# Sheet1.net
KiCad netlist of a schematic drawn in Altium Designer
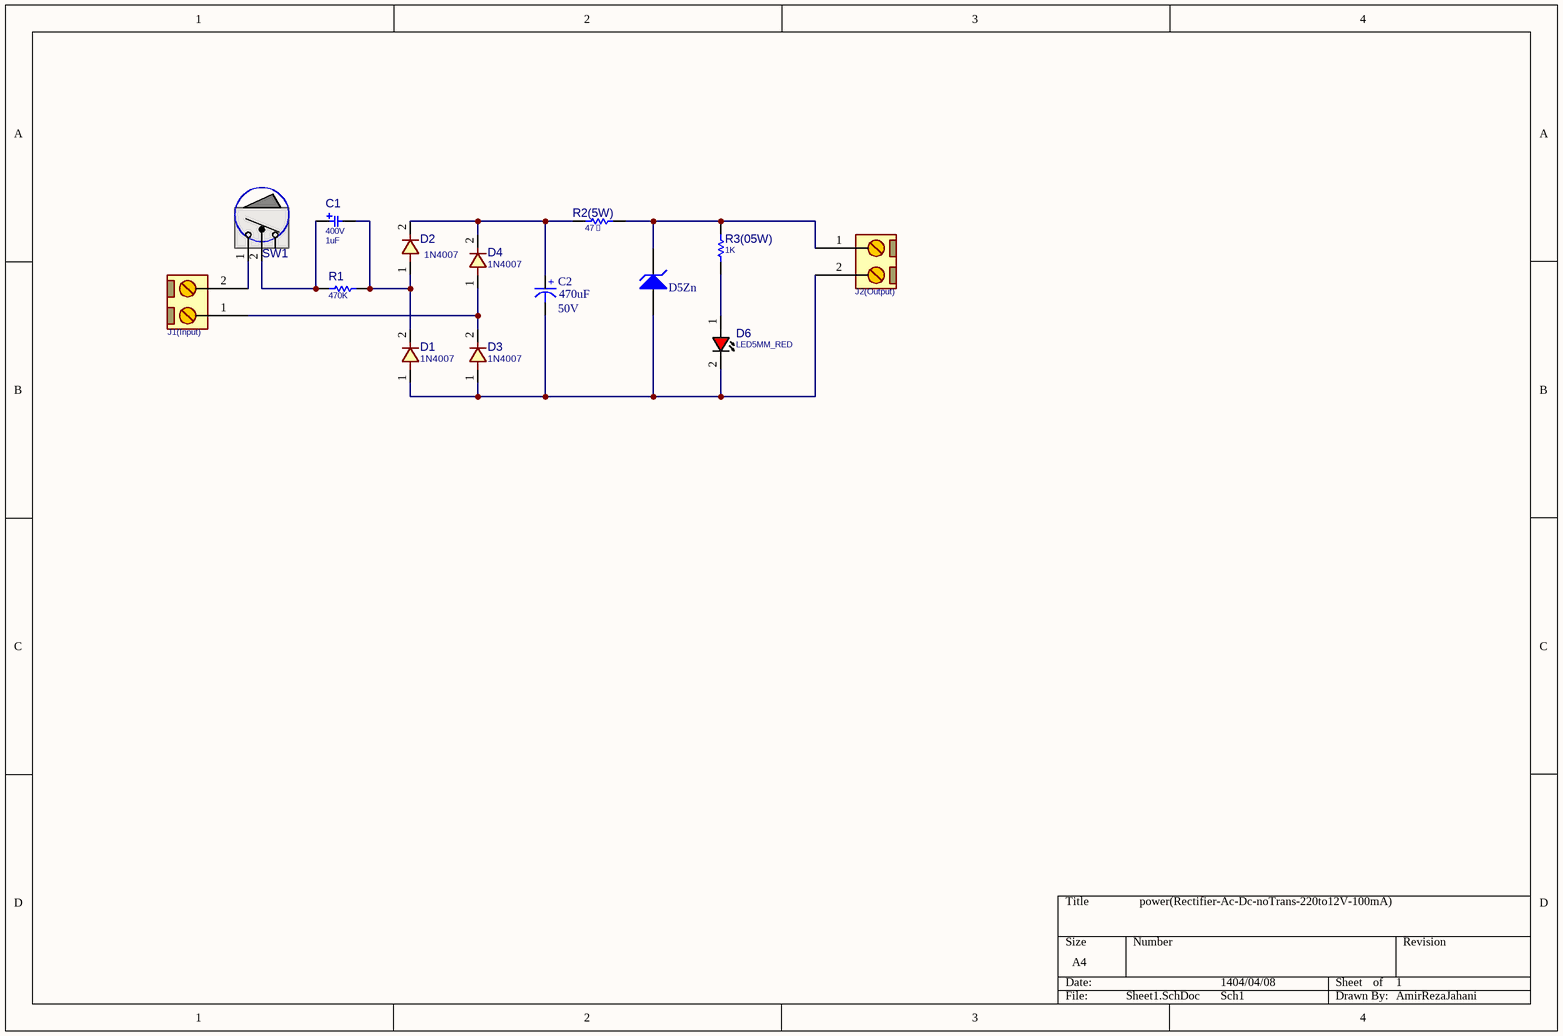
[diagram p0: Sheet1.SchDoc]

(export (version "E")
  (design (tool "Eeschema 10.0.6"))
  (components
    (comp (ref "C1")
      (value "1uF")
      (footprint "C_FLM_22X7H14")
      (description "CAP, THD, FILM,")
      (fields
        (field (name "MANF_P#") "MANF_PART#")
        (field (name "MANF") "MANF")
        (field (name "PARAM2") "400V")
      )
      (libsource (lib "passive_thd") (part "CAP_THD_FLM_0.47uF_400v"))
    )
    (comp (ref "C2")
      (value "470uF")
      (footprint "cap 03")
      (description "Polar Capacitor")
      (fields (field (name "VOLTAGE") "50V") (field (name "DESIGNER") "Saeid Jorablo"))
      (libsource (lib "My_Library") (part "Cap-Polar"))
    )
    (comp (ref "D1")
      (value "1N4007")
      (footprint "D_AX04_DO41")
      (description "DIODE, THD")
      (fields (field (name "MANF") "MANF") (field (name "MANF_P#") "1N4001"))
      (libsource (lib "diode") (part "DIODE_THD"))
    )
    (comp (ref "D2")
      (value "1N4007")
      (footprint "D_AX04_DO41")
      (description "DIODE, THD")
      (fields (field (name "MANF") "MANF") (field (name "MANF_P#") "1N4001"))
      (libsource (lib "diode") (part "DIODE_THD"))
    )
    (comp (ref "D3")
      (value "1N4007")
      (footprint "D_AX04_DO41")
      (description "DIODE, THD")
      (fields (field (name "MANF") "MANF") (field (name "MANF_P#") "1N4001"))
      (libsource (lib "diode") (part "DIODE_THD"))
    )
    (comp (ref "D4")
      (value "1N4007")
      (footprint "D_AX04_DO41")
      (description "DIODE, THD")
      (fields (field (name "MANF") "MANF") (field (name "MANF_P#") "1N4001"))
      (libsource (lib "diode") (part "DIODE_THD"))
    )
    (comp (ref "D5Zn")
      (value "Diode Zener")
      (footprint "Diode 1W")
      (description "Zener Diode")
      (fields (field (name "VOLTAGE") "3.3 V") (field (name "DESIGNER") "Saeid Jorablo"))
      (libsource (lib "My_Library") (part "Diode Zener"))
    )
    (comp (ref "D6")
      (value "LED5MM_RED")
      (footprint "LED5MM_RED")
      (description "LED, THD, 5MM, RED")
      (fields (field (name "MANF") "MANF") (field (name "MANF_P#") "MANF_PART#"))
      (libsource (lib "led(diode)") (part "LED_THD_5MM_RED"))
    )
    (comp (ref "J1(Input)")
      (value "CONN_TB2")
      (footprint "TBG_2")
      (description "CONN, TERMINAL BLOCK, 5.08mm pitch")
      (libsource (lib "conn_terminalB") (part "CONN_TB2"))
    )
    (comp (ref "J2(Output)")
      (value "CONN_TB2")
      (footprint "MSTB_2")
      (description "CONN, PHOENIX MSTB, 5-G, 5.08mm pitch")
      (libsource (lib "conn_terminalB") (part "CONN_MSTB_2"))
    )
    (comp (ref "R1")
      (value "470K")
      (footprint "R025W_AX04")
      (description "RESISTOR, THD")
      (fields (field (name "MANF_P#") "RK73H1ETTP4701F") (field (name "MANF") "KOA SPEER"))
      (libsource (lib "passive_thd") (part "RES_THD"))
    )
    (comp (ref "R2(5W)")
      (value "47ꭥ")
      (footprint "RWW5W")
      (description "RESISTOR, THD")
      (fields (field (name "MANF_P#") "RK73H1ETTP4701F") (field (name "MANF") "KOA SPEER"))
      (libsource (lib "passive_thd") (part "RES_THD"))
    )
    (comp (ref "R3(05W)")
      (value "1K")
      (footprint "R05W_AX05")
      (description "RESISTOR, THD")
      (fields (field (name "MANF_P#") "RK73H1ETTP4701F") (field (name "MANF") "KOA SPEER"))
      (libsource (lib "passive_thd") (part "RES_THD"))
    )
    (comp (ref "SW1")
      (value "ToggleSwitch")
      (footprint "SWRCK_SPST_S_15X10")
      (description "SWITCH, Rocker, SPST, THD, 15x10.5mm")
      (libsource (lib "switch_rocker") (part "SWROK_SPST_R_15X10"))
    )
  )
  (nets
    (net (code "1") (name "Net-(C1-Pad2)") (class "Default")
      (node (ref "C1") (pin "2") (pinfunction "2_2") (pintype "passive"))
      (node (ref "D1") (pin "2") (pinfunction "2_2") (pintype "passive"))
      (node (ref "D2") (pin "1") (pinfunction "1_1") (pintype "passive"))
      (node (ref "R1") (pin "2") (pinfunction "2_2") (pintype "passive"))
    )
    (net (code "2") (name "Net-(C2-+)") (class "Default")
      (node (ref "C2") (pin "1") (pinfunction "+_1") (pintype "passive"))
      (node (ref "D2") (pin "2") (pinfunction "2_2") (pintype "passive"))
      (node (ref "D4") (pin "2") (pinfunction "2_2") (pintype "passive"))
      (node (ref "R2(5W)") (pin "1") (pinfunction "1_1") (pintype "passive"))
    )
    (net (code "3") (name "Net-(C2--)") (class "Default")
      (node (ref "C2") (pin "2") (pinfunction "-_2") (pintype "passive"))
      (node (ref "D1") (pin "1") (pinfunction "1_1") (pintype "passive"))
      (node (ref "D3") (pin "1") (pinfunction "1_1") (pintype "passive"))
      (node (ref "D5Zn") (pin "1") (pinfunction "A_1") (pintype "passive"))
      (node (ref "D6") (pin "2") (pinfunction "CATHODE_2") (pintype "passive"))
      (node (ref "J2(Output)") (pin "2") (pinfunction "2_2") (pintype "passive"))
    )
    (net (code "4") (name "Net-(D3-Pad2)") (class "Default")
      (node (ref "D3") (pin "2") (pinfunction "2_2") (pintype "passive"))
      (node (ref "D4") (pin "1") (pinfunction "1_1") (pintype "passive"))
      (node (ref "J1(Input)") (pin "1") (pinfunction "1_1") (pintype "passive"))
    )
    (net (code "5") (name "Net-(D5Zn-K)") (class "Default")
      (node (ref "D5Zn") (pin "2") (pinfunction "K_2") (pintype "passive"))
      (node (ref "J2(Output)") (pin "1") (pinfunction "1_1") (pintype "passive"))
      (node (ref "R2(5W)") (pin "2") (pinfunction "2_2") (pintype "passive"))
      (node (ref "R3(05W)") (pin "1") (pinfunction "1_1") (pintype "passive"))
    )
    (net (code "6") (name "Net-(D6-ANODE)") (class "Default")
      (node (ref "D6") (pin "1") (pinfunction "ANODE_1") (pintype "passive"))
      (node (ref "R3(05W)") (pin "2") (pinfunction "2_2") (pintype "passive"))
    )
    (net (code "7") (name "Net-(SW1-COM)") (class "Default")
      (node (ref "C1") (pin "1") (pinfunction "1_1") (pintype "passive"))
      (node (ref "R1") (pin "1") (pinfunction "1_1") (pintype "passive"))
      (node (ref "SW1") (pin "2") (pinfunction "COM_2") (pintype "passive"))
    )
    (net (code "8") (name "Net-(SW1-T1)") (class "Default")
      (node (ref "J1(Input)") (pin "2") (pinfunction "2_2") (pintype "passive"))
      (node (ref "SW1") (pin "1") (pinfunction "T1_1") (pintype "passive"))
    )
  )
)
